# satshakit-grbl.net
KiCad netlist of a schematic drawn in EAGLE
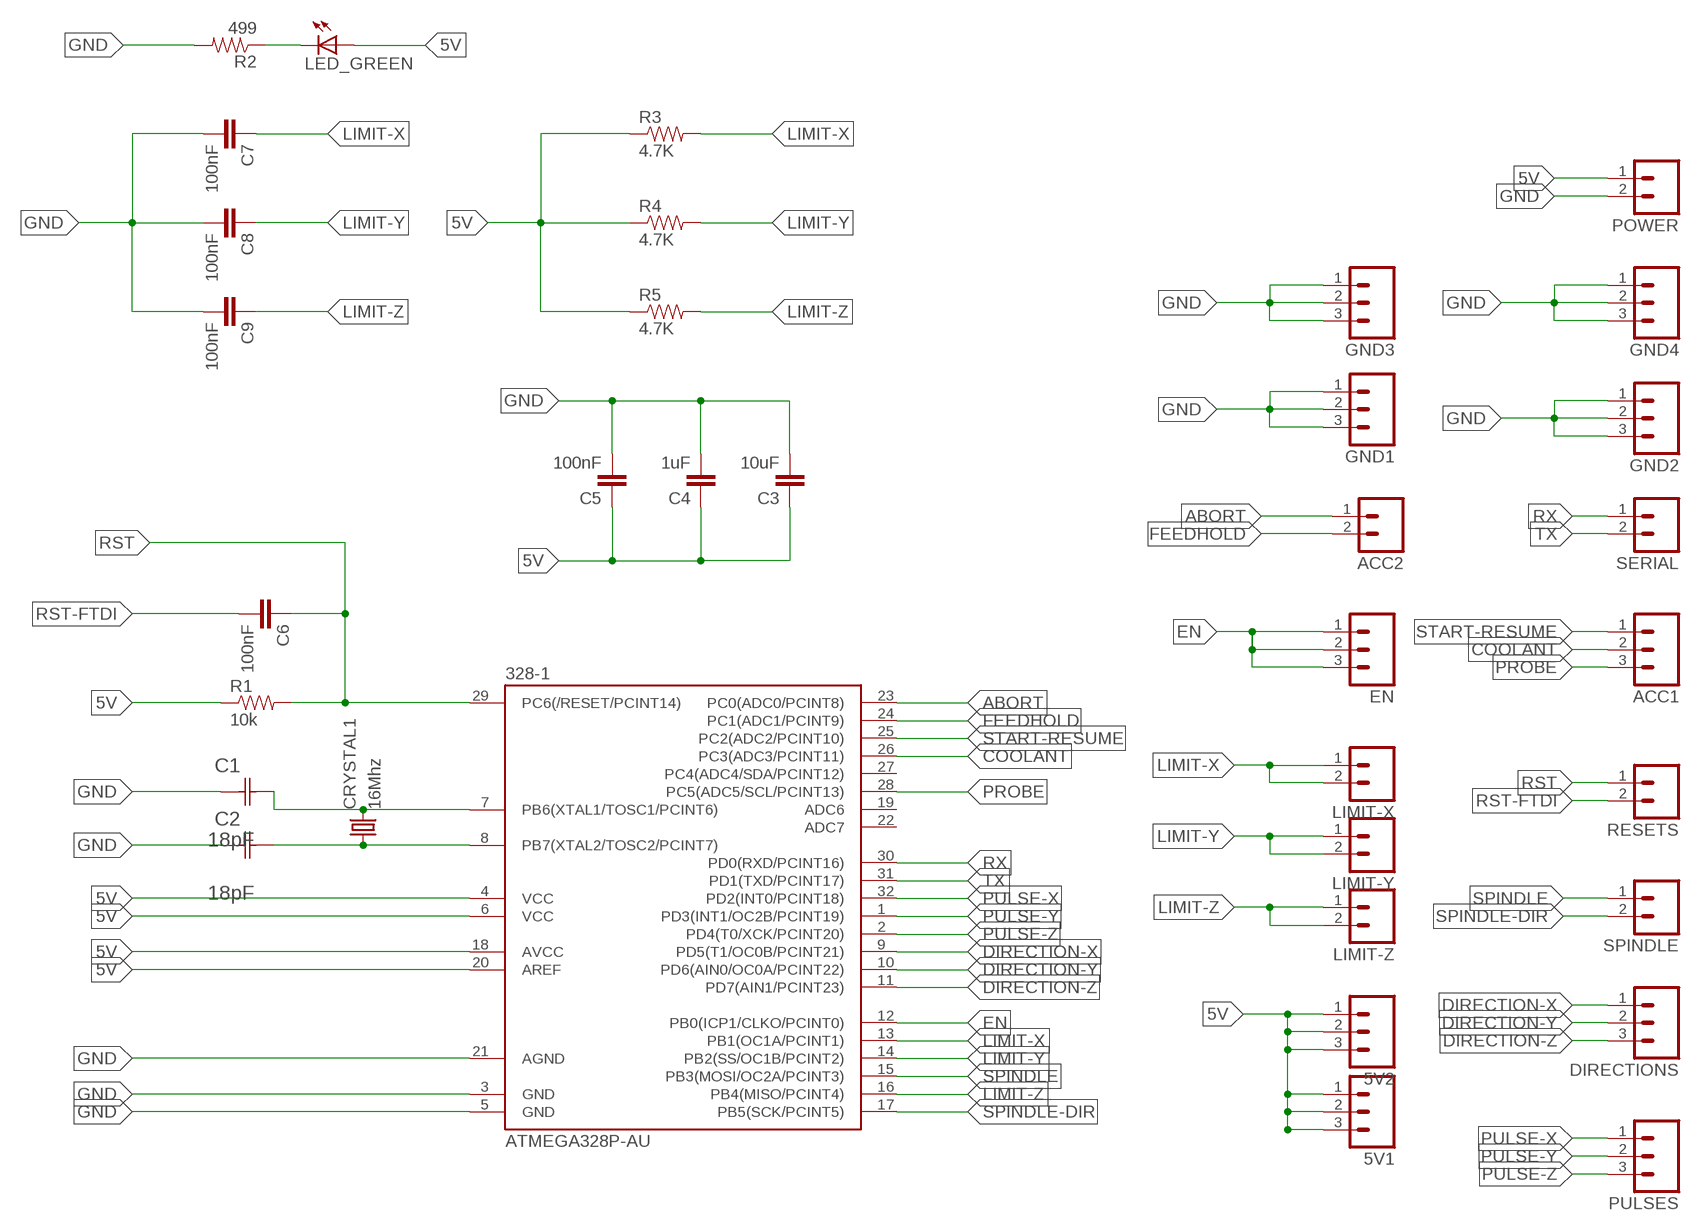
[diagram p0: schematic, sheet 1]

(export (version "E")
  (design (tool "Eeschema 10.0.6"))
  (components
    (comp (ref "5V1")
      (value "M03")
      (footprint "eagle-import:03P")
      (libsource (lib "eagle-import") (part "M03"))
    )
    (comp (ref "5V2")
      (value "M03")
      (footprint "eagle-import:03P")
      (libsource (lib "eagle-import") (part "M03"))
    )
    (comp (ref "328-1")
      (value "ATMEGA328P-AU")
      (footprint "eagle-import:TQFP32-08")
      (libsource (lib "eagle-import") (part "ATMEGA48/88/168-AU"))
    )
    (comp (ref "ACC1")
      (value "M03")
      (footprint "eagle-import:03P")
      (libsource (lib "eagle-import") (part "M03"))
    )
    (comp (ref "ACC2")
      (value "M02")
      (footprint "eagle-import:02P")
      (libsource (lib "eagle-import") (part "M02"))
    )
    (comp (ref "C1")
      (value "18pF")
      (footprint "eagle-import:CAPC3216X178N")
      (fields (field (name "MPN") "0612ZC225MAT2A") (field (name "TOLERANCE") "±20%"))
      (libsource (lib "eagle-import") (part "0612ZC225MAT2A"))
    )
    (comp (ref "C2")
      (value "18pF")
      (footprint "eagle-import:CAPC3216X178N")
      (fields (field (name "MPN") "0612ZC225MAT2A") (field (name "TOLERANCE") "±20%"))
      (libsource (lib "eagle-import") (part "0612ZC225MAT2A"))
    )
    (comp (ref "C3")
      (value "10uF")
      (footprint "eagle-import:1206")
      (libsource (lib "eagle-import") (part "CAP1206"))
    )
    (comp (ref "C4")
      (value "1uF")
      (footprint "eagle-import:1206")
      (libsource (lib "eagle-import") (part "CAP1206"))
    )
    (comp (ref "C5")
      (value "100nF")
      (footprint "eagle-import:1206")
      (libsource (lib "eagle-import") (part "CAP1206"))
    )
    (comp (ref "C6")
      (value "100nF")
      (footprint "eagle-import:1206")
      (libsource (lib "eagle-import") (part "CAP1206"))
    )
    (comp (ref "C7")
      (value "100nF")
      (footprint "eagle-import:1206")
      (libsource (lib "eagle-import") (part "CAP1206"))
    )
    (comp (ref "C8")
      (value "100nF")
      (footprint "eagle-import:1206")
      (libsource (lib "eagle-import") (part "CAP1206"))
    )
    (comp (ref "C9")
      (value "100nF")
      (footprint "eagle-import:1206")
      (libsource (lib "eagle-import") (part "CAP1206"))
    )
    (comp (ref "CRYSTAL1")
      (value "16Mhz")
      (footprint "eagle-import:CSM-7X-DU")
      (libsource (lib "eagle-import") (part "CSM-7X-DU"))
    )
    (comp (ref "DIRECTIONS")
      (value "M03")
      (footprint "eagle-import:03P")
      (libsource (lib "eagle-import") (part "M03"))
    )
    (comp (ref "EN")
      (value "M03")
      (footprint "eagle-import:03P")
      (libsource (lib "eagle-import") (part "M03"))
    )
    (comp (ref "GND1")
      (value "M03")
      (footprint "eagle-import:03P")
      (libsource (lib "eagle-import") (part "M03"))
    )
    (comp (ref "GND2")
      (value "M03")
      (footprint "eagle-import:03P")
      (libsource (lib "eagle-import") (part "M03"))
    )
    (comp (ref "GND3")
      (value "M03")
      (footprint "eagle-import:03P")
      (libsource (lib "eagle-import") (part "M03"))
    )
    (comp (ref "GND4")
      (value "M03")
      (footprint "eagle-import:03P")
      (libsource (lib "eagle-import") (part "M03"))
    )
    (comp (ref "LED_GREEN")
      (value "LED1206")
      (footprint "eagle-import:1206")
      (libsource (lib "eagle-import") (part "LED1206"))
    )
    (comp (ref "LIMIT-X")
      (value "M02")
      (footprint "eagle-import:02P")
      (libsource (lib "eagle-import") (part "M02"))
    )
    (comp (ref "LIMIT-Y")
      (value "M02")
      (footprint "eagle-import:02P")
      (libsource (lib "eagle-import") (part "M02"))
    )
    (comp (ref "LIMIT-Z")
      (value "M02")
      (footprint "eagle-import:02P")
      (libsource (lib "eagle-import") (part "M02"))
    )
    (comp (ref "POWER")
      (value "M02")
      (footprint "eagle-import:02P")
      (libsource (lib "eagle-import") (part "M02"))
    )
    (comp (ref "PULSES")
      (value "M03")
      (footprint "eagle-import:03P")
      (libsource (lib "eagle-import") (part "M03"))
    )
    (comp (ref "R1")
      (value "10k")
      (footprint "eagle-import:1206")
      (libsource (lib "eagle-import") (part "RESISTOR1206"))
    )
    (comp (ref "R2")
      (value "499")
      (footprint "eagle-import:1206")
      (libsource (lib "eagle-import") (part "RESISTOR1206"))
    )
    (comp (ref "R3")
      (value "4.7K")
      (footprint "eagle-import:1206")
      (libsource (lib "eagle-import") (part "RESISTOR1206"))
    )
    (comp (ref "R4")
      (value "4.7K")
      (footprint "eagle-import:1206")
      (libsource (lib "eagle-import") (part "RESISTOR1206"))
    )
    (comp (ref "R5")
      (value "4.7K")
      (footprint "eagle-import:1206")
      (libsource (lib "eagle-import") (part "RESISTOR1206"))
    )
    (comp (ref "RESETS")
      (value "M02")
      (footprint "eagle-import:02P")
      (libsource (lib "eagle-import") (part "M02"))
    )
    (comp (ref "SERIAL")
      (value "M02")
      (footprint "eagle-import:02P")
      (libsource (lib "eagle-import") (part "M02"))
    )
    (comp (ref "SPINDLE")
      (value "M02")
      (footprint "eagle-import:02P")
      (libsource (lib "eagle-import") (part "M02"))
    )
  )
  (nets
    (net (code "1") (name "5V") (class "Default")
      (node (ref "328-1") (pin "18") (pinfunction "AVCC_18") (pintype "passive"))
      (node (ref "328-1") (pin "20") (pinfunction "AREF_20") (pintype "passive"))
      (node (ref "328-1") (pin "4") (pinfunction "VCC_4") (pintype "power_in"))
      (node (ref "328-1") (pin "6") (pinfunction "VCC_6") (pintype "power_in"))
      (node (ref "5V1") (pin "1") (pinfunction "1_1") (pintype "passive"))
      (node (ref "5V1") (pin "2") (pinfunction "2_2") (pintype "passive"))
      (node (ref "5V1") (pin "3") (pinfunction "3_3") (pintype "passive"))
      (node (ref "5V2") (pin "1") (pinfunction "1_1") (pintype "passive"))
      (node (ref "5V2") (pin "2") (pinfunction "2_2") (pintype "passive"))
      (node (ref "5V2") (pin "3") (pinfunction "3_3") (pintype "passive"))
      (node (ref "C3") (pin "1") (pinfunction "1_1") (pintype "passive"))
      (node (ref "C4") (pin "1") (pinfunction "1_1") (pintype "passive"))
      (node (ref "C5") (pin "1") (pinfunction "1_1") (pintype "passive"))
      (node (ref "LED_GREEN") (pin "1") (pinfunction "A_1") (pintype "passive"))
      (node (ref "POWER") (pin "1") (pinfunction "1_1") (pintype "passive"))
      (node (ref "R1") (pin "1") (pinfunction "1_1") (pintype "passive"))
      (node (ref "R3") (pin "1") (pinfunction "1_1") (pintype "passive"))
      (node (ref "R4") (pin "1") (pinfunction "1_1") (pintype "passive"))
      (node (ref "R5") (pin "1") (pinfunction "1_1") (pintype "passive"))
    )
    (net (code "2") (name "ABORT") (class "Default")
      (node (ref "328-1") (pin "23") (pinfunction "PC0(ADC0/PCINT8)_23") (pintype "bidirectional"))
      (node (ref "ACC2") (pin "1") (pinfunction "1_1") (pintype "passive"))
    )
    (net (code "3") (name "COOLANT") (class "Default")
      (node (ref "328-1") (pin "26") (pinfunction "PC3(ADC3/PCINT11)_26") (pintype "bidirectional"))
      (node (ref "ACC1") (pin "2") (pinfunction "2_2") (pintype "passive"))
    )
    (net (code "4") (name "DIRECTION-X") (class "Default")
      (node (ref "328-1") (pin "9") (pinfunction "PD5(T1/OC0B/PCINT21)_9") (pintype "bidirectional"))
      (node (ref "DIRECTIONS") (pin "1") (pinfunction "1_1") (pintype "passive"))
    )
    (net (code "5") (name "DIRECTION-Y") (class "Default")
      (node (ref "328-1") (pin "10") (pinfunction "PD6(AIN0/OC0A/PCINT22)_10") (pintype "bidirectional"))
      (node (ref "DIRECTIONS") (pin "2") (pinfunction "2_2") (pintype "passive"))
    )
    (net (code "6") (name "DIRECTION-Z") (class "Default")
      (node (ref "328-1") (pin "11") (pinfunction "PD7(AIN1/PCINT23)_11") (pintype "bidirectional"))
      (node (ref "DIRECTIONS") (pin "3") (pinfunction "3_3") (pintype "passive"))
    )
    (net (code "7") (name "EN") (class "Default")
      (node (ref "328-1") (pin "12") (pinfunction "PB0(ICP1/CLKO/PCINT0)_12") (pintype "bidirectional"))
      (node (ref "EN") (pin "1") (pinfunction "1_1") (pintype "passive"))
      (node (ref "EN") (pin "2") (pinfunction "2_2") (pintype "passive"))
      (node (ref "EN") (pin "3") (pinfunction "3_3") (pintype "passive"))
    )
    (net (code "8") (name "FEEDHOLD") (class "Default")
      (node (ref "328-1") (pin "24") (pinfunction "PC1(ADC1/PCINT9)_24") (pintype "bidirectional"))
      (node (ref "ACC2") (pin "2") (pinfunction "2_2") (pintype "passive"))
    )
    (net (code "9") (name "GND") (class "Default")
      (node (ref "328-1") (pin "21") (pinfunction "AGND_21") (pintype "power_in"))
      (node (ref "328-1") (pin "3") (pinfunction "GND_3") (pintype "power_in"))
      (node (ref "328-1") (pin "5") (pinfunction "GND_5") (pintype "power_in"))
      (node (ref "C1") (pin "1") (pinfunction "C1_1") (pintype "passive"))
      (node (ref "C2") (pin "1") (pinfunction "C1_1") (pintype "passive"))
      (node (ref "C3") (pin "2") (pinfunction "2_2") (pintype "passive"))
      (node (ref "C4") (pin "2") (pinfunction "2_2") (pintype "passive"))
      (node (ref "C5") (pin "2") (pinfunction "2_2") (pintype "passive"))
      (node (ref "C7") (pin "2") (pinfunction "2_2") (pintype "passive"))
      (node (ref "C8") (pin "2") (pinfunction "2_2") (pintype "passive"))
      (node (ref "C9") (pin "2") (pinfunction "2_2") (pintype "passive"))
      (node (ref "GND1") (pin "1") (pinfunction "1_1") (pintype "passive"))
      (node (ref "GND1") (pin "2") (pinfunction "2_2") (pintype "passive"))
      (node (ref "GND1") (pin "3") (pinfunction "3_3") (pintype "passive"))
      (node (ref "GND2") (pin "1") (pinfunction "1_1") (pintype "passive"))
      (node (ref "GND2") (pin "2") (pinfunction "2_2") (pintype "passive"))
      (node (ref "GND2") (pin "3") (pinfunction "3_3") (pintype "passive"))
      (node (ref "GND3") (pin "1") (pinfunction "1_1") (pintype "passive"))
      (node (ref "GND3") (pin "2") (pinfunction "2_2") (pintype "passive"))
      (node (ref "GND3") (pin "3") (pinfunction "3_3") (pintype "passive"))
      (node (ref "GND4") (pin "1") (pinfunction "1_1") (pintype "passive"))
      (node (ref "GND4") (pin "2") (pinfunction "2_2") (pintype "passive"))
      (node (ref "GND4") (pin "3") (pinfunction "3_3") (pintype "passive"))
      (node (ref "POWER") (pin "2") (pinfunction "2_2") (pintype "passive"))
      (node (ref "R2") (pin "2") (pinfunction "2_2") (pintype "passive"))
    )
    (net (code "10") (name "LIMIT-X") (class "Default")
      (node (ref "328-1") (pin "13") (pinfunction "PB1(OC1A/PCINT1)_13") (pintype "bidirectional"))
      (node (ref "C7") (pin "1") (pinfunction "1_1") (pintype "passive"))
      (node (ref "LIMIT-X") (pin "1") (pinfunction "1_1") (pintype "passive"))
      (node (ref "LIMIT-X") (pin "2") (pinfunction "2_2") (pintype "passive"))
      (node (ref "R3") (pin "2") (pinfunction "2_2") (pintype "passive"))
    )
    (net (code "11") (name "LIMIT-Y") (class "Default")
      (node (ref "328-1") (pin "14") (pinfunction "PB2(SS/OC1B/PCINT2)_14") (pintype "bidirectional"))
      (node (ref "C8") (pin "1") (pinfunction "1_1") (pintype "passive"))
      (node (ref "LIMIT-Y") (pin "1") (pinfunction "1_1") (pintype "passive"))
      (node (ref "LIMIT-Y") (pin "2") (pinfunction "2_2") (pintype "passive"))
      (node (ref "R4") (pin "2") (pinfunction "2_2") (pintype "passive"))
    )
    (net (code "12") (name "LIMIT-Z") (class "Default")
      (node (ref "328-1") (pin "16") (pinfunction "PB4(MISO/PCINT4)_16") (pintype "bidirectional"))
      (node (ref "C9") (pin "1") (pinfunction "1_1") (pintype "passive"))
      (node (ref "LIMIT-Z") (pin "1") (pinfunction "1_1") (pintype "passive"))
      (node (ref "LIMIT-Z") (pin "2") (pinfunction "2_2") (pintype "passive"))
      (node (ref "R5") (pin "2") (pinfunction "2_2") (pintype "passive"))
    )
    (net (code "13") (name "Net-(328-1-PB6(XTAL1{slash}TOSC1{slash}PCINT6))") (class "Default")
      (node (ref "328-1") (pin "7") (pinfunction "PB6(XTAL1/TOSC1/PCINT6)_7") (pintype "bidirectional"))
      (node (ref "C1") (pin "2") (pinfunction "C2_2") (pintype "passive"))
      (node (ref "CRYSTAL1") (pin "2") (pinfunction "2_2") (pintype "passive"))
    )
    (net (code "14") (name "Net-(328-1-PB7(XTAL2{slash}TOSC2{slash}PCINT7))") (class "Default")
      (node (ref "328-1") (pin "8") (pinfunction "PB7(XTAL2/TOSC2/PCINT7)_8") (pintype "bidirectional"))
      (node (ref "C2") (pin "2") (pinfunction "C2_2") (pintype "passive"))
      (node (ref "CRYSTAL1") (pin "1") (pinfunction "1_1") (pintype "passive"))
    )
    (net (code "15") (name "Net-(LED_GREEN-C)") (class "Default")
      (node (ref "LED_GREEN") (pin "2") (pinfunction "C_2") (pintype "passive"))
      (node (ref "R2") (pin "1") (pinfunction "1_1") (pintype "passive"))
    )
    (net (code "16") (name "PROBE") (class "Default")
      (node (ref "328-1") (pin "28") (pinfunction "PC5(ADC5/SCL/PCINT13)_28") (pintype "bidirectional"))
      (node (ref "ACC1") (pin "3") (pinfunction "3_3") (pintype "passive"))
    )
    (net (code "17") (name "PULSE-X") (class "Default")
      (node (ref "328-1") (pin "32") (pinfunction "PD2(INT0/PCINT18)_32") (pintype "bidirectional"))
      (node (ref "PULSES") (pin "1") (pinfunction "1_1") (pintype "passive"))
    )
    (net (code "18") (name "PULSE-Y") (class "Default")
      (node (ref "328-1") (pin "1") (pinfunction "PD3(INT1/OC2B/PCINT19)_1") (pintype "bidirectional"))
      (node (ref "PULSES") (pin "2") (pinfunction "2_2") (pintype "passive"))
    )
    (net (code "19") (name "PULSE-Z") (class "Default")
      (node (ref "328-1") (pin "2") (pinfunction "PD4(T0/XCK/PCINT20)_2") (pintype "bidirectional"))
      (node (ref "PULSES") (pin "3") (pinfunction "3_3") (pintype "passive"))
    )
    (net (code "20") (name "RST") (class "Default")
      (node (ref "328-1") (pin "29") (pinfunction "PC6(/RESET/PCINT14)_29") (pintype "bidirectional"))
      (node (ref "C6") (pin "1") (pinfunction "1_1") (pintype "passive"))
      (node (ref "R1") (pin "2") (pinfunction "2_2") (pintype "passive"))
      (node (ref "RESETS") (pin "1") (pinfunction "1_1") (pintype "passive"))
    )
    (net (code "21") (name "RST-FTDI") (class "Default")
      (node (ref "C6") (pin "2") (pinfunction "2_2") (pintype "passive"))
      (node (ref "RESETS") (pin "2") (pinfunction "2_2") (pintype "passive"))
    )
    (net (code "22") (name "RX") (class "Default")
      (node (ref "328-1") (pin "30") (pinfunction "PD0(RXD/PCINT16)_30") (pintype "bidirectional"))
      (node (ref "SERIAL") (pin "1") (pinfunction "1_1") (pintype "passive"))
    )
    (net (code "23") (name "SPINDLE") (class "Default")
      (node (ref "328-1") (pin "15") (pinfunction "PB3(MOSI/OC2A/PCINT3)_15") (pintype "bidirectional"))
      (node (ref "SPINDLE") (pin "1") (pinfunction "1_1") (pintype "passive"))
    )
    (net (code "24") (name "SPINDLE-DIR") (class "Default")
      (node (ref "328-1") (pin "17") (pinfunction "PB5(SCK/PCINT5)_17") (pintype "bidirectional"))
      (node (ref "SPINDLE") (pin "2") (pinfunction "2_2") (pintype "passive"))
    )
    (net (code "25") (name "START-RESUME") (class "Default")
      (node (ref "328-1") (pin "25") (pinfunction "PC2(ADC2/PCINT10)_25") (pintype "bidirectional"))
      (node (ref "ACC1") (pin "1") (pinfunction "1_1") (pintype "passive"))
    )
    (net (code "26") (name "TX") (class "Default")
      (node (ref "328-1") (pin "31") (pinfunction "PD1(TXD/PCINT17)_31") (pintype "bidirectional"))
      (node (ref "SERIAL") (pin "2") (pinfunction "2_2") (pintype "passive"))
    )
    (net (code "27") (name "unconnected-(328-1-ADC6-Pad19)") (class "Default")
      (node (ref "328-1") (pin "19") (pinfunction "ADC6_19") (pintype "passive"))
    )
    (net (code "28") (name "unconnected-(328-1-ADC7-Pad22)") (class "Default")
      (node (ref "328-1") (pin "22") (pinfunction "ADC7_22") (pintype "passive"))
    )
    (net (code "29") (name "unconnected-(328-1-PC4(ADC4{slash}SDA{slash}PCINT12)-Pad27)") (class "Default")
      (node (ref "328-1") (pin "27") (pinfunction "PC4(ADC4/SDA/PCINT12)_27") (pintype "bidirectional"))
    )
  )
)
